# startlamp.net
KiCad netlist of a schematic drawn in EAGLE
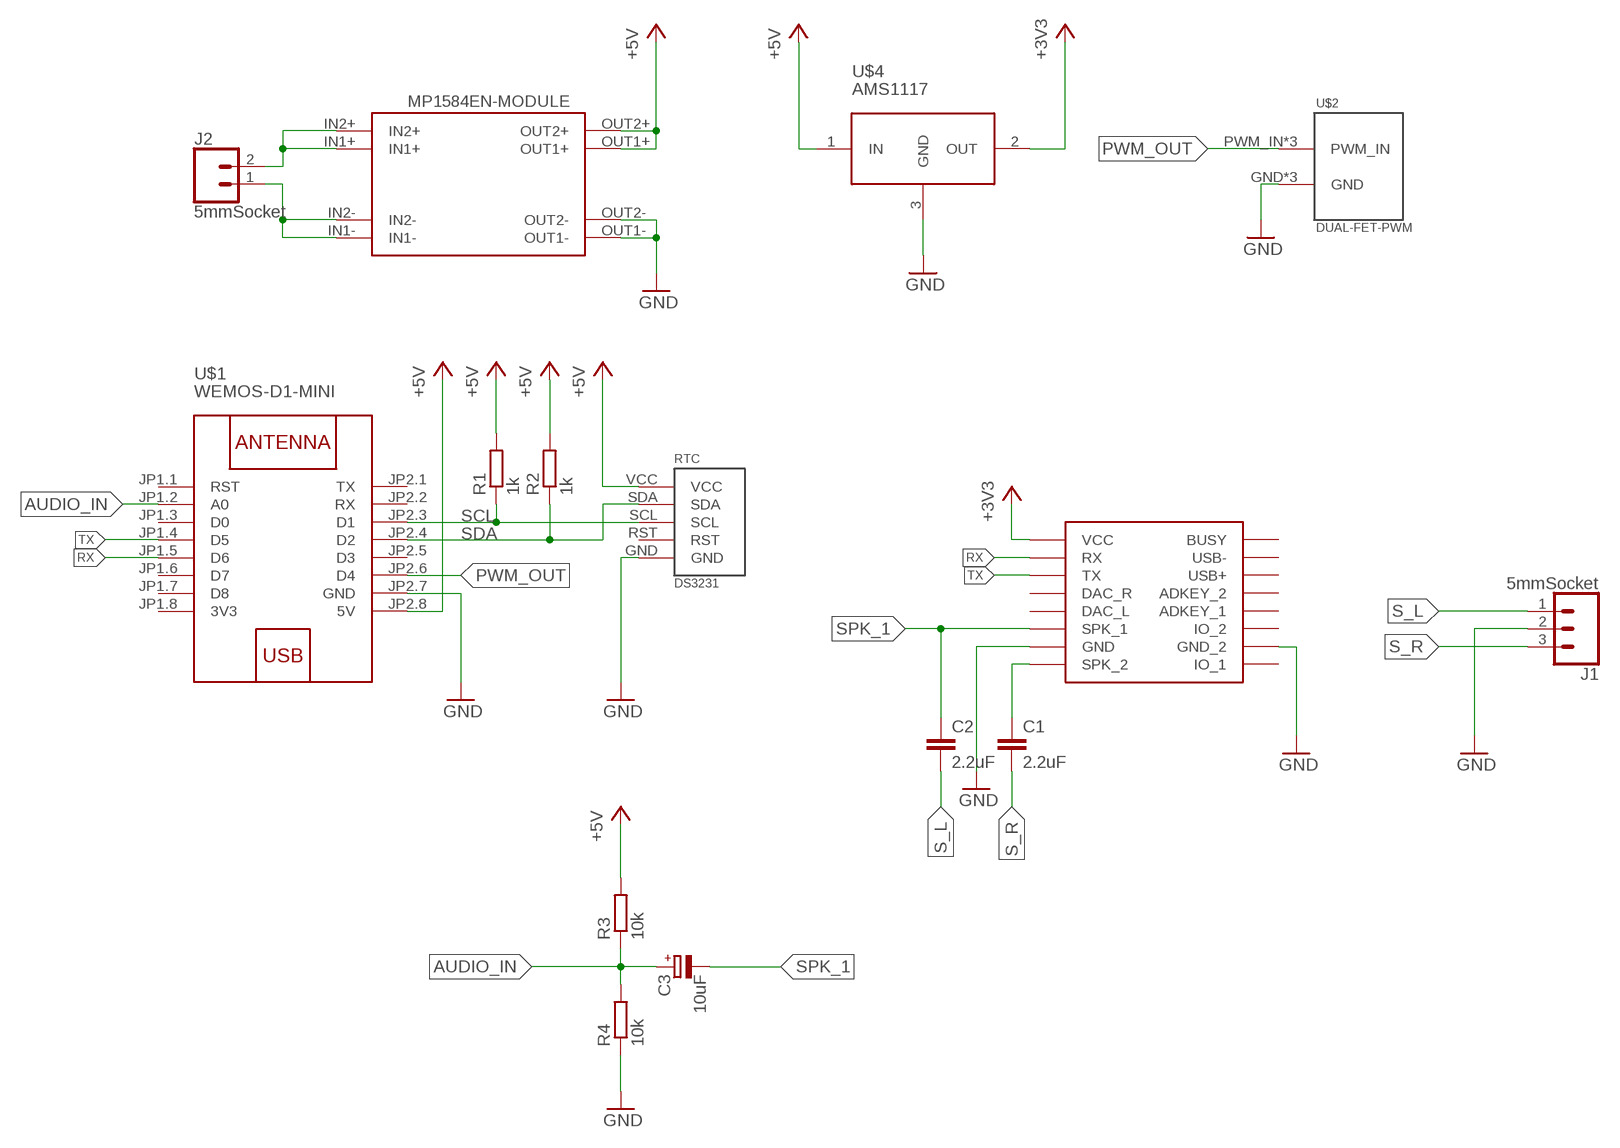
[diagram p0: schematic, sheet 1]

(export (version "E")
  (design (tool "Eeschema 10.0.6"))
  (components
    (comp (ref "C1")
      (value "2.2uF")
      (footprint "eagle-import:C050-024X044")
      (libsource (lib "eagle-import") (part "C-EU050-024X044"))
    )
    (comp (ref "C2")
      (value "2.2uF")
      (footprint "eagle-import:C050-024X044")
      (libsource (lib "eagle-import") (part "C-EU050-024X044"))
    )
    (comp (ref "C3")
      (value "10uF")
      (footprint "eagle-import:E5-4")
      (libsource (lib "eagle-import") (part "CPOL-EUE5-4"))
    )
    (comp (ref "J1")
      (value "5mmSocket")
      (footprint "eagle-import:SCREWTERMINAL-5MM-3")
      (libsource (lib "eagle-import") (part "CONN_03-SCREW-5MM"))
    )
    (comp (ref "J2")
      (value "5mmSocket")
      (footprint "eagle-import:SCREWTERMINAL-5MM-2")
      (libsource (lib "eagle-import") (part "CONN_025MM"))
    )
    (comp (ref "R1")
      (value "1k")
      (footprint "eagle-import:0204V")
      (libsource (lib "eagle-import") (part "R-EU_0204/2V"))
    )
    (comp (ref "R2")
      (value "1k")
      (footprint "eagle-import:0204V")
      (libsource (lib "eagle-import") (part "R-EU_0204/2V"))
    )
    (comp (ref "R3")
      (value "10k")
      (footprint "eagle-import:0204V")
      (libsource (lib "eagle-import") (part "R-EU_0204/2V"))
    )
    (comp (ref "R4")
      (value "10k")
      (footprint "eagle-import:0204V")
      (libsource (lib "eagle-import") (part "R-EU_0204/2V"))
    )
    (comp (ref "RTC")
      (value "DS3231")
      (footprint "eagle-import:RTC-MINI")
      (libsource (lib "eagle-import") (part "RTC-MINI"))
    )
    (comp (ref "U$1")
      (value "WEMOS-D1-MINI")
      (footprint "eagle-import:WEMOS-D1-MINI")
      (libsource (lib "eagle-import") (part "WEMOS-D1-MINI"))
    )
    (comp (ref "U$2")
      (value "DUAL-FET-PWM")
      (footprint "eagle-import:DUAL-FET-PWM")
      (libsource (lib "eagle-import") (part "DUAL-FET-PWM"))
    )
    (comp (ref "U$3")
      (value "DFPLAYER")
      (footprint "eagle-import:DFPLAYER")
      (libsource (lib "eagle-import") (part "DFPLAYER"))
    )
    (comp (ref "U$4")
      (value "AMS1117")
      (footprint "eagle-import:REG-AMS1117-3P#V")
      (libsource (lib "eagle-import") (part "REG-AMS1117-3P-#V3.3V"))
    )
    (comp (ref "U1")
      (value "MP1584")
      (footprint "eagle-import:DSUN_NEW")
      (libsource (lib "eagle-import") (part "MP1584EN-DC-DC-CONVERTOR"))
    )
  )
  (nets
    (net (code "1") (name "+3V3") (class "Default")
      (node (ref "U$3") (pin "VCC") (pinfunction "VCC_VCC") (pintype "power_in"))
      (node (ref "U$4") (pin "2") (pinfunction "OUT_2") (pintype "bidirectional"))
    )
    (net (code "2") (name "+5V") (class "Default")
      (node (ref "R1") (pin "2") (pinfunction "2_2") (pintype "passive"))
      (node (ref "R2") (pin "2") (pinfunction "2_2") (pintype "passive"))
      (node (ref "R3") (pin "2") (pinfunction "2_2") (pintype "passive"))
      (node (ref "RTC") (pin "VCC") (pinfunction "VCC_VCC") (pintype "power_in"))
      (node (ref "U$1") (pin "JP2.8") (pinfunction "5V_JP2.8") (pintype "power_in"))
      (node (ref "U$4") (pin "1") (pinfunction "IN_1") (pintype "bidirectional"))
      (node (ref "U1") (pin "OUT1+") (pinfunction "OUT1+_OUT1+") (pintype "bidirectional"))
      (node (ref "U1") (pin "OUT2+") (pinfunction "OUT2+_OUT2+") (pintype "bidirectional"))
    )
    (net (code "3") (name "/3V3") (class "Default")
      (node (ref "U$1") (pin "JP1.8") (pinfunction "3V3_JP1.8") (pintype "power_in"))
    )
    (net (code "4") (name "/SCL") (class "Default")
      (node (ref "R1") (pin "1") (pinfunction "1_1") (pintype "passive"))
      (node (ref "RTC") (pin "SCL") (pinfunction "SCL_SCL") (pintype "bidirectional"))
      (node (ref "U$1") (pin "JP2.3") (pinfunction "D1_JP2.3") (pintype "bidirectional"))
    )
    (net (code "5") (name "/SDA") (class "Default")
      (node (ref "R2") (pin "1") (pinfunction "1_1") (pintype "passive"))
      (node (ref "RTC") (pin "SDA") (pinfunction "SDA_SDA") (pintype "power_in"))
      (node (ref "U$1") (pin "JP2.4") (pinfunction "D2_JP2.4") (pintype "bidirectional"))
    )
    (net (code "6") (name "AUDIO_IN") (class "Default")
      (node (ref "C3") (pin "+") (pinfunction "+_+") (pintype "passive"))
      (node (ref "R3") (pin "1") (pinfunction "1_1") (pintype "passive"))
      (node (ref "R4") (pin "2") (pinfunction "2_2") (pintype "passive"))
      (node (ref "U$1") (pin "JP1.2") (pinfunction "A0_JP1.2") (pintype "bidirectional"))
    )
    (net (code "7") (name "GND") (class "Default")
      (node (ref "J1") (pin "2") (pinfunction "2_2") (pintype "passive"))
      (node (ref "R4") (pin "1") (pinfunction "1_1") (pintype "passive"))
      (node (ref "RTC") (pin "GND") (pinfunction "GND_GND") (pintype "bidirectional"))
      (node (ref "U$1") (pin "JP2.7") (pinfunction "GND_JP2.7") (pintype "power_in"))
      (node (ref "U$2") (pin "GND") (pinfunction "GND_GND") (pintype "power_in"))
      (node (ref "U$2") (pin "GND2") (pinfunction "GND_GND2") (pintype "power_in"))
      (node (ref "U$2") (pin "GND3") (pinfunction "GND_GND3") (pintype "power_in"))
      (node (ref "U$3") (pin "GND") (pinfunction "GND_GND") (pintype "power_in"))
      (node (ref "U$3") (pin "GND_2") (pinfunction "GND_2_GND_2") (pintype "power_in"))
      (node (ref "U$4") (pin "3") (pinfunction "GND_3") (pintype "bidirectional"))
      (node (ref "U1") (pin "OUT1-") (pinfunction "OUT1-_OUT1-") (pintype "bidirectional"))
      (node (ref "U1") (pin "OUT2-") (pinfunction "OUT2-_OUT2-") (pintype "bidirectional"))
    )
    (net (code "8") (name "Net-(J2-Pad1)") (class "Default")
      (node (ref "J2") (pin "1") (pinfunction "1_1") (pintype "passive"))
      (node (ref "U1") (pin "IN1-") (pinfunction "IN1-_IN1-") (pintype "bidirectional"))
      (node (ref "U1") (pin "IN2-") (pinfunction "IN2-_IN2-") (pintype "bidirectional"))
    )
    (net (code "9") (name "Net-(J2-Pad2)") (class "Default")
      (node (ref "J2") (pin "2") (pinfunction "2_2") (pintype "passive"))
      (node (ref "U1") (pin "IN1+") (pinfunction "IN1+_IN1+") (pintype "bidirectional"))
      (node (ref "U1") (pin "IN2+") (pinfunction "IN2+_IN2+") (pintype "bidirectional"))
    )
    (net (code "10") (name "Net-(U$3-SPK_2)") (class "Default")
      (node (ref "C1") (pin "1") (pinfunction "1_1") (pintype "passive"))
      (node (ref "U$3") (pin "SPK2") (pinfunction "SPK_2_SPK2") (pintype "bidirectional"))
    )
    (net (code "11") (name "PWM_OUT") (class "Default")
      (node (ref "U$1") (pin "JP2.6") (pinfunction "D4_JP2.6") (pintype "bidirectional"))
      (node (ref "U$2") (pin "PWM_IN") (pinfunction "PWM_IN_PWM_IN") (pintype "input"))
      (node (ref "U$2") (pin "PWM_IN2") (pinfunction "PWM_IN_PWM_IN2") (pintype "input"))
      (node (ref "U$2") (pin "PWM_IN3") (pinfunction "PWM_IN_PWM_IN3") (pintype "input"))
    )
    (net (code "12") (name "RX") (class "Default")
      (node (ref "U$1") (pin "JP1.5") (pinfunction "D6_JP1.5") (pintype "bidirectional"))
      (node (ref "U$3") (pin "RX") (pinfunction "RX_RX") (pintype "bidirectional"))
    )
    (net (code "13") (name "SPK_1") (class "Default")
      (node (ref "C2") (pin "1") (pinfunction "1_1") (pintype "passive"))
      (node (ref "C3") (pin "-") (pinfunction "-_-") (pintype "passive"))
      (node (ref "U$3") (pin "SPK1") (pinfunction "SPK_1_SPK1") (pintype "bidirectional"))
    )
    (net (code "14") (name "S_L") (class "Default")
      (node (ref "C2") (pin "2") (pinfunction "2_2") (pintype "passive"))
      (node (ref "J1") (pin "1") (pinfunction "1_1") (pintype "passive"))
    )
    (net (code "15") (name "S_R") (class "Default")
      (node (ref "C1") (pin "2") (pinfunction "2_2") (pintype "passive"))
      (node (ref "J1") (pin "3") (pinfunction "3_3") (pintype "passive"))
    )
    (net (code "16") (name "TX") (class "Default")
      (node (ref "U$1") (pin "JP1.4") (pinfunction "D5_JP1.4") (pintype "bidirectional"))
      (node (ref "U$3") (pin "TX") (pinfunction "TX_TX") (pintype "bidirectional"))
    )
    (net (code "17") (name "unconnected-(RTC-PadRST)") (class "Default")
      (node (ref "RTC") (pin "RST") (pinfunction "RST_RST") (pintype "bidirectional"))
    )
    (net (code "18") (name "unconnected-(U$1-D0-PadJP1.3)") (class "Default")
      (node (ref "U$1") (pin "JP1.3") (pinfunction "D0_JP1.3") (pintype "bidirectional"))
    )
    (net (code "19") (name "unconnected-(U$1-D3-PadJP2.5)") (class "Default")
      (node (ref "U$1") (pin "JP2.5") (pinfunction "D3_JP2.5") (pintype "bidirectional"))
    )
    (net (code "20") (name "unconnected-(U$1-D7-PadJP1.6)") (class "Default")
      (node (ref "U$1") (pin "JP1.6") (pinfunction "D7_JP1.6") (pintype "bidirectional"))
    )
    (net (code "21") (name "unconnected-(U$1-D8-PadJP1.7)") (class "Default")
      (node (ref "U$1") (pin "JP1.7") (pinfunction "D8_JP1.7") (pintype "bidirectional"))
    )
    (net (code "22") (name "unconnected-(U$1-RST-PadJP1.1)") (class "Default")
      (node (ref "U$1") (pin "JP1.1") (pinfunction "RST_JP1.1") (pintype "bidirectional"))
    )
    (net (code "23") (name "unconnected-(U$1-RX-PadJP2.2)") (class "Default")
      (node (ref "U$1") (pin "JP2.2") (pinfunction "RX_JP2.2") (pintype "bidirectional"))
    )
    (net (code "24") (name "unconnected-(U$1-TX-PadJP2.1)") (class "Default")
      (node (ref "U$1") (pin "JP2.1") (pinfunction "TX_JP2.1") (pintype "bidirectional"))
    )
    (net (code "25") (name "unconnected-(U$3-ADKEY_1-PadADKEY1)") (class "Default")
      (node (ref "U$3") (pin "ADKEY1") (pinfunction "ADKEY_1_ADKEY1") (pintype "bidirectional"))
    )
    (net (code "26") (name "unconnected-(U$3-ADKEY_2-PadADKEY2)") (class "Default")
      (node (ref "U$3") (pin "ADKEY2") (pinfunction "ADKEY_2_ADKEY2") (pintype "bidirectional"))
    )
    (net (code "27") (name "unconnected-(U$3-IO_1-PadIO1)") (class "Default")
      (node (ref "U$3") (pin "IO1") (pinfunction "IO_1_IO1") (pintype "bidirectional"))
    )
    (net (code "28") (name "unconnected-(U$3-IO_2-PadIO2)") (class "Default")
      (node (ref "U$3") (pin "IO2") (pinfunction "IO_2_IO2") (pintype "bidirectional"))
    )
    (net (code "29") (name "unconnected-(U$3-PadBUSY)") (class "Default")
      (node (ref "U$3") (pin "BUSY") (pinfunction "BUSY_BUSY") (pintype "bidirectional"))
    )
    (net (code "30") (name "unconnected-(U$3-PadDAC_L)") (class "Default")
      (node (ref "U$3") (pin "DAC_L") (pinfunction "DAC_L_DAC_L") (pintype "bidirectional"))
    )
    (net (code "31") (name "unconnected-(U$3-PadDAC_R)") (class "Default")
      (node (ref "U$3") (pin "DAC_R") (pinfunction "DAC_R_DAC_R") (pintype "bidirectional"))
    )
    (net (code "32") (name "unconnected-(U$3-PadUSB+)") (class "Default")
      (node (ref "U$3") (pin "USB+") (pinfunction "USB+_USB+") (pintype "bidirectional"))
    )
    (net (code "33") (name "unconnected-(U$3-PadUSB-)") (class "Default")
      (node (ref "U$3") (pin "USB-") (pinfunction "USB-_USB-") (pintype "bidirectional"))
    )
  )
)
